# TopLevelDesign.net
KiCad netlist of a schematic drawn in Altium Designer
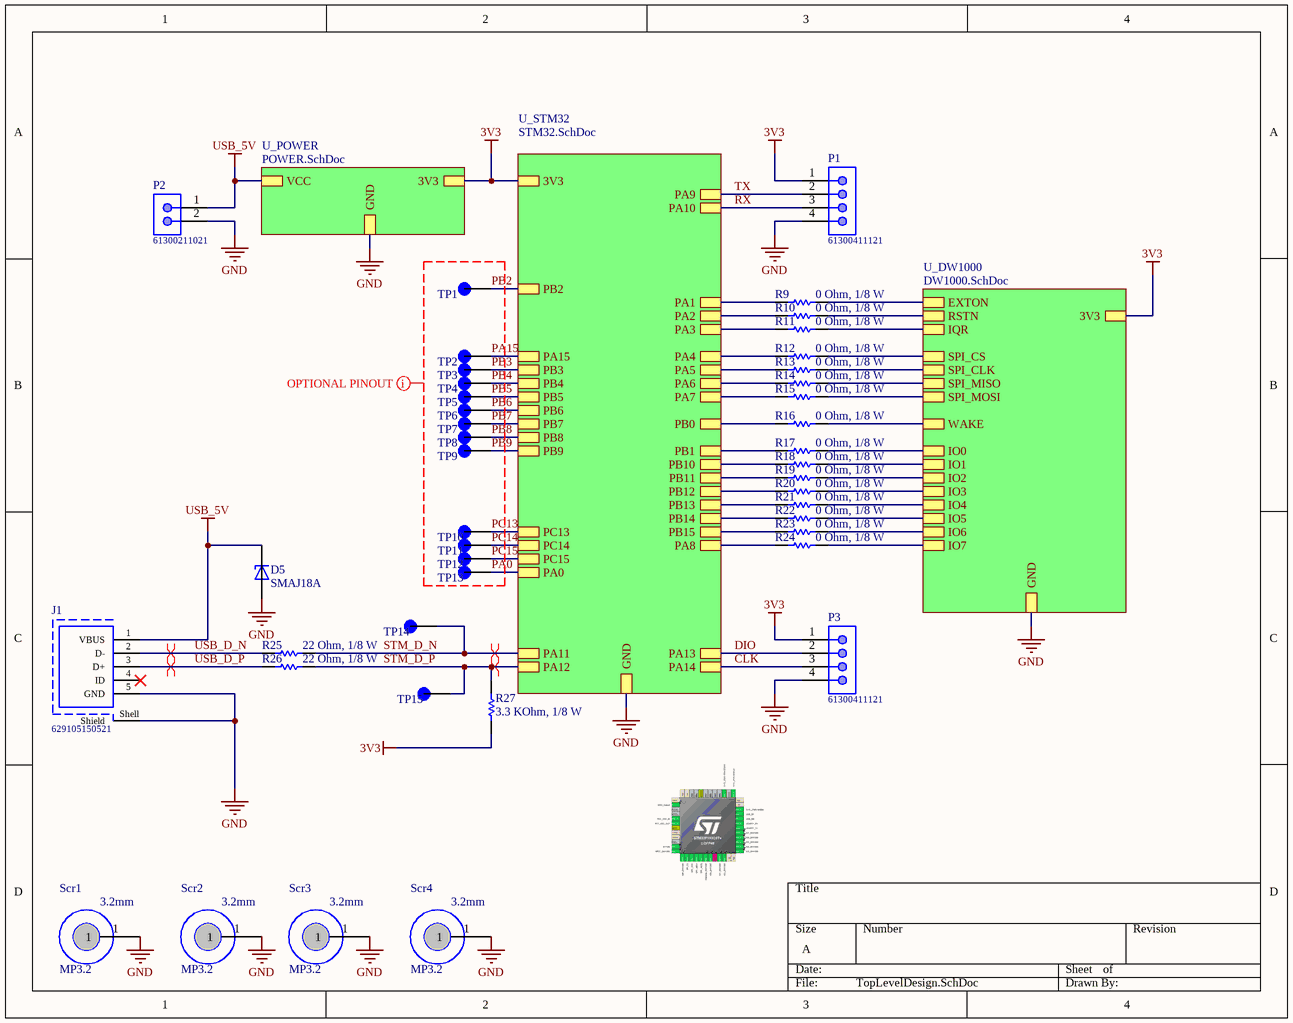
[diagram p0: TopLevelDesign.SchDoc]

(export (version "E")
  (design (tool "Eeschema 10.0.6"))
  (components
    (comp (ref "D5")
      (value "SMAJ18A")
      (footprint "DIOM4325X250N")
      (description "400W, 21.1V, 5%, Unidirectional, TVS")
      (fields (field (name "MF") "Taiwan Semiconductor"))
      (libsource (lib "Tin Tran") (part "SMAJ18A"))
    )
    (comp (ref "J1")
      (value "629105150521")
      (footprint "629105150521")
      (description "Micro USB 2.0 Type B Receptacle WR-COM, Horizontal, SMT, with Pegs, High Current at Pin 1 & Pin 5")
      (fields (field (name "PUBLISHER") "Wurth Elektronik"))
      (libsource (lib "Tin Tran") (part "651305142821"))
    )
    (comp (ref "P1")
      (value "61300411121")
      (footprint "61300411121")
      (description "WR-PHD Pin Header, THT, pitch 2.54mm, Single Row, Vertical, 4p")
      (fields (field (name "MANUFACTURER") "Wurth Elektronik"))
      (libsource (lib "Tin Tran") (part "61300411121"))
    )
    (comp (ref "P2")
      (value "61300211021")
      (footprint "61300211021")
      (description "WR-PHD Pin Header, THT, pitch 2.54mm, Single Row, Angled, 2p")
      (fields (field (name "MANUFACTURER") "Wurth Elektronik"))
      (libsource (lib "Tin Tran") (part "61300211121"))
    )
    (comp (ref "P3")
      (value "61300411121")
      (footprint "61300411121")
      (description "WR-PHD Pin Header, THT, pitch 2.54mm, Single Row, Vertical, 4p")
      (fields (field (name "MANUFACTURER") "Wurth Elektronik"))
      (libsource (lib "Tin Tran") (part "61300411121"))
    )
    (comp (ref "R9")
      (value "0 Ohm, 1/8 W")
      (footprint "RESISTOR_0805")
      (description "RES, size 0805, 0 Ohm, 1/8 W")
      (fields (field (name "Comment") "0008050001"))
      (libsource (lib "Tin Tran") (part "0008052035_1"))
    )
    (comp (ref "R10")
      (value "0 Ohm, 1/8 W")
      (footprint "RESISTOR_0805")
      (description "RES, size 0805, 0 Ohm, 1/8 W")
      (fields (field (name "Comment") "0008050001"))
      (libsource (lib "Tin Tran") (part "0008052035_1"))
    )
    (comp (ref "R11")
      (value "0 Ohm, 1/8 W")
      (footprint "RESISTOR_0805")
      (description "RES, size 0805, 0 Ohm, 1/8 W")
      (fields (field (name "Comment") "0008050001"))
      (libsource (lib "Tin Tran") (part "0008052035_1"))
    )
    (comp (ref "R12")
      (value "0 Ohm, 1/8 W")
      (footprint "RESISTOR_0805")
      (description "RES, size 0805, 0 Ohm, 1/8 W")
      (fields (field (name "Comment") "0008050001"))
      (libsource (lib "Tin Tran") (part "0008052035_1"))
    )
    (comp (ref "R13")
      (value "0 Ohm, 1/8 W")
      (footprint "RESISTOR_0805")
      (description "RES, size 0805, 0 Ohm, 1/8 W")
      (fields (field (name "Comment") "0008050001"))
      (libsource (lib "Tin Tran") (part "0008052035_1"))
    )
    (comp (ref "R14")
      (value "0 Ohm, 1/8 W")
      (footprint "RESISTOR_0805")
      (description "RES, size 0805, 0 Ohm, 1/8 W")
      (fields (field (name "Comment") "0008050001"))
      (libsource (lib "Tin Tran") (part "0008052035_1"))
    )
    (comp (ref "R15")
      (value "0 Ohm, 1/8 W")
      (footprint "RESISTOR_0805")
      (description "RES, size 0805, 0 Ohm, 1/8 W")
      (fields (field (name "Comment") "0008050001"))
      (libsource (lib "Tin Tran") (part "0008052035_1"))
    )
    (comp (ref "R16")
      (value "0 Ohm, 1/8 W")
      (footprint "RESISTOR_0805")
      (description "RES, size 0805, 0 Ohm, 1/8 W")
      (fields (field (name "Comment") "0008050001"))
      (libsource (lib "Tin Tran") (part "0008052035_1"))
    )
    (comp (ref "R17")
      (value "0 Ohm, 1/8 W")
      (footprint "RESISTOR_0805")
      (description "RES, size 0805, 0 Ohm, 1/8 W")
      (fields (field (name "Comment") "0008050001"))
      (libsource (lib "Tin Tran") (part "0008052035_1"))
    )
    (comp (ref "R18")
      (value "0 Ohm, 1/8 W")
      (footprint "RESISTOR_0805")
      (description "RES, size 0805, 0 Ohm, 1/8 W")
      (fields (field (name "Comment") "0008050001"))
      (libsource (lib "Tin Tran") (part "0008052035_1"))
    )
    (comp (ref "R19")
      (value "0 Ohm, 1/8 W")
      (footprint "RESISTOR_0805")
      (description "RES, size 0805, 0 Ohm, 1/8 W")
      (fields (field (name "Comment") "0008050001"))
      (libsource (lib "Tin Tran") (part "0008052035_1"))
    )
    (comp (ref "R20")
      (value "0 Ohm, 1/8 W")
      (footprint "RESISTOR_0805")
      (description "RES, size 0805, 0 Ohm, 1/8 W")
      (fields (field (name "Comment") "0008050001"))
      (libsource (lib "Tin Tran") (part "0008052035_1"))
    )
    (comp (ref "R21")
      (value "0 Ohm, 1/8 W")
      (footprint "RESISTOR_0805")
      (description "RES, size 0805, 0 Ohm, 1/8 W")
      (fields (field (name "Comment") "0008050001"))
      (libsource (lib "Tin Tran") (part "0008052035_1"))
    )
    (comp (ref "R22")
      (value "0 Ohm, 1/8 W")
      (footprint "RESISTOR_0805")
      (description "RES, size 0805, 0 Ohm, 1/8 W")
      (fields (field (name "Comment") "0008050001"))
      (libsource (lib "Tin Tran") (part "0008052035_1"))
    )
    (comp (ref "R23")
      (value "0 Ohm, 1/8 W")
      (footprint "RESISTOR_0805")
      (description "RES, size 0805, 0 Ohm, 1/8 W")
      (fields (field (name "Comment") "0008050001"))
      (libsource (lib "Tin Tran") (part "0008052035_1"))
    )
    (comp (ref "R24")
      (value "0 Ohm, 1/8 W")
      (footprint "RESISTOR_0805")
      (description "RES, size 0805, 0 Ohm, 1/8 W")
      (fields (field (name "Comment") "0008050001"))
      (libsource (lib "Tin Tran") (part "0008052035_1"))
    )
    (comp (ref "R25")
      (value "22 Ohm, 1/8 W")
      (footprint "RESISTOR_0805")
      (description "RES, size 0805, 22 Ohm, 1/8 W")
      (fields (field (name "Comment") "0008052205"))
      (libsource (lib "Tin Tran") (part "0008052035_1"))
    )
    (comp (ref "R26")
      (value "22 Ohm, 1/8 W")
      (footprint "RESISTOR_0805")
      (description "RES, size 0805, 22 Ohm, 1/8 W")
      (fields (field (name "Comment") "0008052205"))
      (libsource (lib "Tin Tran") (part "0008052035_1"))
    )
    (comp (ref "R27")
      (value "3.3 KOhm, 1/8 W")
      (footprint "RESISTOR_0805")
      (description "RES, size 0805, 3.3 KOhm, 1/8 W")
      (fields (field (name "Comment") "0008053325"))
      (libsource (lib "Tin Tran") (part "0008052035_1"))
    )
    (comp (ref "Scr1") (value "MP3.2") (footprint "MP3.2") (libsource (lib "Tin Tran") (part "MP3.2")))
    (comp (ref "Scr2") (value "MP3.2") (footprint "MP3.2") (libsource (lib "Tin Tran") (part "MP3.2")))
    (comp (ref "Scr3") (value "MP3.2") (footprint "MP3.2") (libsource (lib "Tin Tran") (part "MP3.2")))
    (comp (ref "Scr4") (value "MP3.2") (footprint "MP3.2") (libsource (lib "Tin Tran") (part "MP3.2")))
    (comp (ref "TP1")
      (value "Keystone_SMD")
      (footprint "KEYSTONE_5019")
      (description "Test Point, Mini, SMT, Phos Bronze/Silver, 1000pc Tape & Reel")
      (fields (field (name "MP") "5019") (field (name "MF") "Keystone Electronics"))
      (libsource (lib "Tin Tran") (part "5019"))
    )
    (comp (ref "TP2")
      (value "Keystone_SMD")
      (footprint "KEYSTONE_5019")
      (description "Test Point, Mini, SMT, Phos Bronze/Silver, 1000pc Tape & Reel")
      (fields (field (name "MP") "5019") (field (name "MF") "Keystone Electronics"))
      (libsource (lib "Tin Tran") (part "5019"))
    )
    (comp (ref "TP3")
      (value "Keystone_SMD")
      (footprint "KEYSTONE_5019")
      (description "Test Point, Mini, SMT, Phos Bronze/Silver, 1000pc Tape & Reel")
      (fields (field (name "MP") "5019") (field (name "MF") "Keystone Electronics"))
      (libsource (lib "Tin Tran") (part "5019"))
    )
    (comp (ref "TP4")
      (value "Keystone_SMD")
      (footprint "KEYSTONE_5019")
      (description "Test Point, Mini, SMT, Phos Bronze/Silver, 1000pc Tape & Reel")
      (fields (field (name "MP") "5019") (field (name "MF") "Keystone Electronics"))
      (libsource (lib "Tin Tran") (part "5019"))
    )
    (comp (ref "TP5")
      (value "Keystone_SMD")
      (footprint "KEYSTONE_5019")
      (description "Test Point, Mini, SMT, Phos Bronze/Silver, 1000pc Tape & Reel")
      (fields (field (name "MP") "5019") (field (name "MF") "Keystone Electronics"))
      (libsource (lib "Tin Tran") (part "5019"))
    )
    (comp (ref "TP6")
      (value "Keystone_SMD")
      (footprint "KEYSTONE_5019")
      (description "Test Point, Mini, SMT, Phos Bronze/Silver, 1000pc Tape & Reel")
      (fields (field (name "MP") "5019") (field (name "MF") "Keystone Electronics"))
      (libsource (lib "Tin Tran") (part "5019"))
    )
    (comp (ref "TP7")
      (value "Keystone_SMD")
      (footprint "KEYSTONE_5019")
      (description "Test Point, Mini, SMT, Phos Bronze/Silver, 1000pc Tape & Reel")
      (fields (field (name "MP") "5019") (field (name "MF") "Keystone Electronics"))
      (libsource (lib "Tin Tran") (part "5019"))
    )
    (comp (ref "TP8")
      (value "Keystone_SMD")
      (footprint "KEYSTONE_5019")
      (description "Test Point, Mini, SMT, Phos Bronze/Silver, 1000pc Tape & Reel")
      (fields (field (name "MP") "5019") (field (name "MF") "Keystone Electronics"))
      (libsource (lib "Tin Tran") (part "5019"))
    )
    (comp (ref "TP9")
      (value "Keystone_SMD")
      (footprint "KEYSTONE_5019")
      (description "Test Point, Mini, SMT, Phos Bronze/Silver, 1000pc Tape & Reel")
      (fields (field (name "MP") "5019") (field (name "MF") "Keystone Electronics"))
      (libsource (lib "Tin Tran") (part "5019"))
    )
    (comp (ref "TP10")
      (value "Keystone_SMD")
      (footprint "KEYSTONE_5019")
      (description "Test Point, Mini, SMT, Phos Bronze/Silver, 1000pc Tape & Reel")
      (fields (field (name "MP") "5019") (field (name "MF") "Keystone Electronics"))
      (libsource (lib "Tin Tran") (part "5019"))
    )
    (comp (ref "TP11")
      (value "Keystone_SMD")
      (footprint "KEYSTONE_5019")
      (description "Test Point, Mini, SMT, Phos Bronze/Silver, 1000pc Tape & Reel")
      (fields (field (name "MP") "5019") (field (name "MF") "Keystone Electronics"))
      (libsource (lib "Tin Tran") (part "5019"))
    )
    (comp (ref "TP12")
      (value "Keystone_SMD")
      (footprint "KEYSTONE_5019")
      (description "Test Point, Mini, SMT, Phos Bronze/Silver, 1000pc Tape & Reel")
      (fields (field (name "MP") "5019") (field (name "MF") "Keystone Electronics"))
      (libsource (lib "Tin Tran") (part "5019"))
    )
    (comp (ref "TP13")
      (value "Keystone_SMD")
      (footprint "KEYSTONE_5019")
      (description "Test Point, Mini, SMT, Phos Bronze/Silver, 1000pc Tape & Reel")
      (fields (field (name "MP") "5019") (field (name "MF") "Keystone Electronics"))
      (libsource (lib "Tin Tran") (part "5019"))
    )
    (comp (ref "TP14")
      (value "Keystone_SMD")
      (footprint "KEYSTONE_5019")
      (description "Test Point, Mini, SMT, Phos Bronze/Silver, 1000pc Tape & Reel")
      (fields (field (name "MP") "5019") (field (name "MF") "Keystone Electronics"))
      (libsource (lib "Tin Tran") (part "5019"))
    )
    (comp (ref "TP15")
      (value "Keystone_SMD")
      (footprint "KEYSTONE_5019")
      (description "Test Point, Mini, SMT, Phos Bronze/Silver, 1000pc Tape & Reel")
      (fields (field (name "MP") "5019") (field (name "MF") "Keystone Electronics"))
      (libsource (lib "Tin Tran") (part "5019"))
    )
  )
  (nets
    (net (code "1") (name "/CLK") (class "Default")
      (node (ref "P3") (pin "3") (pinfunction "3_3") (pintype "passive"))
    )
    (net (code "2") (name "/DIO") (class "Default")
      (node (ref "P3") (pin "2") (pinfunction "2_2") (pintype "passive"))
    )
    (net (code "3") (name "/EXTON") (class "Default")
      (node (ref "R9") (pin "2") (pinfunction "2_2") (pintype "passive"))
    )
    (net (code "4") (name "/IO0") (class "Default")
      (node (ref "R17") (pin "2") (pinfunction "2_2") (pintype "passive"))
    )
    (net (code "5") (name "/IO1") (class "Default")
      (node (ref "R18") (pin "2") (pinfunction "2_2") (pintype "passive"))
    )
    (net (code "6") (name "/IO2") (class "Default")
      (node (ref "R19") (pin "2") (pinfunction "2_2") (pintype "passive"))
    )
    (net (code "7") (name "/IO3") (class "Default")
      (node (ref "R20") (pin "2") (pinfunction "2_2") (pintype "passive"))
    )
    (net (code "8") (name "/IO4") (class "Default")
      (node (ref "R21") (pin "2") (pinfunction "2_2") (pintype "passive"))
    )
    (net (code "9") (name "/IO5") (class "Default")
      (node (ref "R22") (pin "2") (pinfunction "2_2") (pintype "passive"))
    )
    (net (code "10") (name "/IO6") (class "Default")
      (node (ref "R23") (pin "2") (pinfunction "2_2") (pintype "passive"))
    )
    (net (code "11") (name "/IO7") (class "Default")
      (node (ref "R24") (pin "2") (pinfunction "2_2") (pintype "passive"))
    )
    (net (code "12") (name "/IQR") (class "Default")
      (node (ref "R11") (pin "2") (pinfunction "2_2") (pintype "passive"))
    )
    (net (code "13") (name "/PA0") (class "Default")
      (node (ref "TP13") (pin "TP") (pinfunction "TP_TP") (pintype "passive"))
    )
    (net (code "14") (name "/PA1") (class "Default")
      (node (ref "R9") (pin "1") (pinfunction "1_1") (pintype "passive"))
    )
    (net (code "15") (name "/PA2") (class "Default")
      (node (ref "R10") (pin "1") (pinfunction "1_1") (pintype "passive"))
    )
    (net (code "16") (name "/PA3") (class "Default")
      (node (ref "R11") (pin "1") (pinfunction "1_1") (pintype "passive"))
    )
    (net (code "17") (name "/PA4") (class "Default")
      (node (ref "R12") (pin "1") (pinfunction "1_1") (pintype "passive"))
    )
    (net (code "18") (name "/PA5") (class "Default")
      (node (ref "R13") (pin "1") (pinfunction "1_1") (pintype "passive"))
    )
    (net (code "19") (name "/PA6") (class "Default")
      (node (ref "R14") (pin "1") (pinfunction "1_1") (pintype "passive"))
    )
    (net (code "20") (name "/PA7") (class "Default")
      (node (ref "R15") (pin "1") (pinfunction "1_1") (pintype "passive"))
    )
    (net (code "21") (name "/PA8") (class "Default")
      (node (ref "R24") (pin "1") (pinfunction "1_1") (pintype "passive"))
    )
    (net (code "22") (name "/PA15") (class "Default")
      (node (ref "TP2") (pin "TP") (pinfunction "TP_TP") (pintype "passive"))
    )
    (net (code "23") (name "/PB0") (class "Default")
      (node (ref "R16") (pin "1") (pinfunction "1_1") (pintype "passive"))
    )
    (net (code "24") (name "/PB1") (class "Default")
      (node (ref "R17") (pin "1") (pinfunction "1_1") (pintype "passive"))
    )
    (net (code "25") (name "/PB2") (class "Default")
      (node (ref "TP1") (pin "TP") (pinfunction "TP_TP") (pintype "passive"))
    )
    (net (code "26") (name "/PB3") (class "Default")
      (node (ref "TP3") (pin "TP") (pinfunction "TP_TP") (pintype "passive"))
    )
    (net (code "27") (name "/PB4") (class "Default")
      (node (ref "TP4") (pin "TP") (pinfunction "TP_TP") (pintype "passive"))
    )
    (net (code "28") (name "/PB5") (class "Default")
      (node (ref "TP5") (pin "TP") (pinfunction "TP_TP") (pintype "passive"))
    )
    (net (code "29") (name "/PB6") (class "Default")
      (node (ref "TP6") (pin "TP") (pinfunction "TP_TP") (pintype "passive"))
    )
    (net (code "30") (name "/PB7") (class "Default")
      (node (ref "TP7") (pin "TP") (pinfunction "TP_TP") (pintype "passive"))
    )
    (net (code "31") (name "/PB8") (class "Default")
      (node (ref "TP8") (pin "TP") (pinfunction "TP_TP") (pintype "passive"))
    )
    (net (code "32") (name "/PB9") (class "Default")
      (node (ref "TP9") (pin "TP") (pinfunction "TP_TP") (pintype "passive"))
    )
    (net (code "33") (name "/PB10") (class "Default")
      (node (ref "R18") (pin "1") (pinfunction "1_1") (pintype "passive"))
    )
    (net (code "34") (name "/PB11") (class "Default")
      (node (ref "R19") (pin "1") (pinfunction "1_1") (pintype "passive"))
    )
    (net (code "35") (name "/PB12") (class "Default")
      (node (ref "R20") (pin "1") (pinfunction "1_1") (pintype "passive"))
    )
    (net (code "36") (name "/PB13") (class "Default")
      (node (ref "R21") (pin "1") (pinfunction "1_1") (pintype "passive"))
    )
    (net (code "37") (name "/PB14") (class "Default")
      (node (ref "R22") (pin "1") (pinfunction "1_1") (pintype "passive"))
    )
    (net (code "38") (name "/PB15") (class "Default")
      (node (ref "R23") (pin "1") (pinfunction "1_1") (pintype "passive"))
    )
    (net (code "39") (name "/PC13") (class "Default")
      (node (ref "TP10") (pin "TP") (pinfunction "TP_TP") (pintype "passive"))
    )
    (net (code "40") (name "/PC14") (class "Default")
      (node (ref "TP11") (pin "TP") (pinfunction "TP_TP") (pintype "passive"))
    )
    (net (code "41") (name "/PC15") (class "Default")
      (node (ref "TP12") (pin "TP") (pinfunction "TP_TP") (pintype "passive"))
    )
    (net (code "42") (name "/RSTN") (class "Default")
      (node (ref "R10") (pin "2") (pinfunction "2_2") (pintype "passive"))
    )
    (net (code "43") (name "/RX") (class "Default")
      (node (ref "P1") (pin "3") (pinfunction "3_3") (pintype "passive"))
    )
    (net (code "44") (name "/SPI_CLK") (class "Default")
      (node (ref "R13") (pin "2") (pinfunction "2_2") (pintype "passive"))
    )
    (net (code "45") (name "/SPI_CS") (class "Default")
      (node (ref "R12") (pin "2") (pinfunction "2_2") (pintype "passive"))
    )
    (net (code "46") (name "/SPI_MISO") (class "Default")
      (node (ref "R14") (pin "2") (pinfunction "2_2") (pintype "passive"))
    )
    (net (code "47") (name "/SPI_MOSI") (class "Default")
      (node (ref "R15") (pin "2") (pinfunction "2_2") (pintype "passive"))
    )
    (net (code "48") (name "/STM_D_N") (class "Default")
      (node (ref "R25") (pin "2") (pinfunction "2_2") (pintype "passive"))
      (node (ref "TP14") (pin "TP") (pinfunction "TP_TP") (pintype "passive"))
    )
    (net (code "49") (name "/STM_D_P") (class "Default")
      (node (ref "R26") (pin "2") (pinfunction "2_2") (pintype "passive"))
      (node (ref "R27") (pin "2") (pinfunction "2_2") (pintype "passive"))
      (node (ref "TP15") (pin "TP") (pinfunction "TP_TP") (pintype "passive"))
    )
    (net (code "50") (name "/TX") (class "Default")
      (node (ref "P1") (pin "2") (pinfunction "2_2") (pintype "passive"))
    )
    (net (code "51") (name "/USB_D_N") (class "Default")
      (node (ref "J1") (pin "2") (pinfunction "D-_2") (pintype "passive"))
      (node (ref "R25") (pin "1") (pinfunction "1_1") (pintype "passive"))
    )
    (net (code "52") (name "/USB_D_P") (class "Default")
      (node (ref "J1") (pin "3") (pinfunction "D+_3") (pintype "passive"))
      (node (ref "R26") (pin "1") (pinfunction "1_1") (pintype "passive"))
    )
    (net (code "53") (name "/WAKE") (class "Default")
      (node (ref "R16") (pin "2") (pinfunction "2_2") (pintype "passive"))
    )
    (net (code "54") (name "3V3") (class "Default")
      (node (ref "P1") (pin "1") (pinfunction "1_1") (pintype "passive"))
      (node (ref "P3") (pin "1") (pinfunction "1_1") (pintype "passive"))
      (node (ref "R27") (pin "1") (pinfunction "1_1") (pintype "passive"))
    )
    (net (code "55") (name "GND") (class "Default")
      (node (ref "D5") (pin "A") (pinfunction "A_A") (pintype "passive"))
      (node (ref "J1") (pin "5") (pinfunction "GND_5") (pintype "passive"))
      (node (ref "J1") (pin "Shell") (pinfunction "Shield_Shell") (pintype "passive"))
      (node (ref "P1") (pin "4") (pinfunction "4_4") (pintype "passive"))
      (node (ref "P2") (pin "2") (pinfunction "2_2") (pintype "passive"))
      (node (ref "P3") (pin "4") (pinfunction "4_4") (pintype "passive"))
      (node (ref "Scr1") (pin "1") (pinfunction "1_1") (pintype "passive"))
      (node (ref "Scr2") (pin "1") (pinfunction "1_1") (pintype "passive"))
      (node (ref "Scr3") (pin "1") (pinfunction "1_1") (pintype "passive"))
      (node (ref "Scr4") (pin "1") (pinfunction "1_1") (pintype "passive"))
    )
    (net (code "56") (name "USB_5V") (class "Default")
      (node (ref "D5") (pin "C") (pinfunction "C_C") (pintype "passive"))
      (node (ref "J1") (pin "1") (pinfunction "VBUS_1") (pintype "passive"))
      (node (ref "P2") (pin "1") (pinfunction "1_1") (pintype "passive"))
    )
    (net (code "57") (name "unconnected-(J1-ID-Pad4)") (class "Default")
      (node (ref "J1") (pin "4") (pinfunction "ID_4") (pintype "passive+no_connect"))
    )
  )
)
